# STAC_Test_Board_v1_USB.net
KiCad netlist of a schematic drawn in Altium Designer
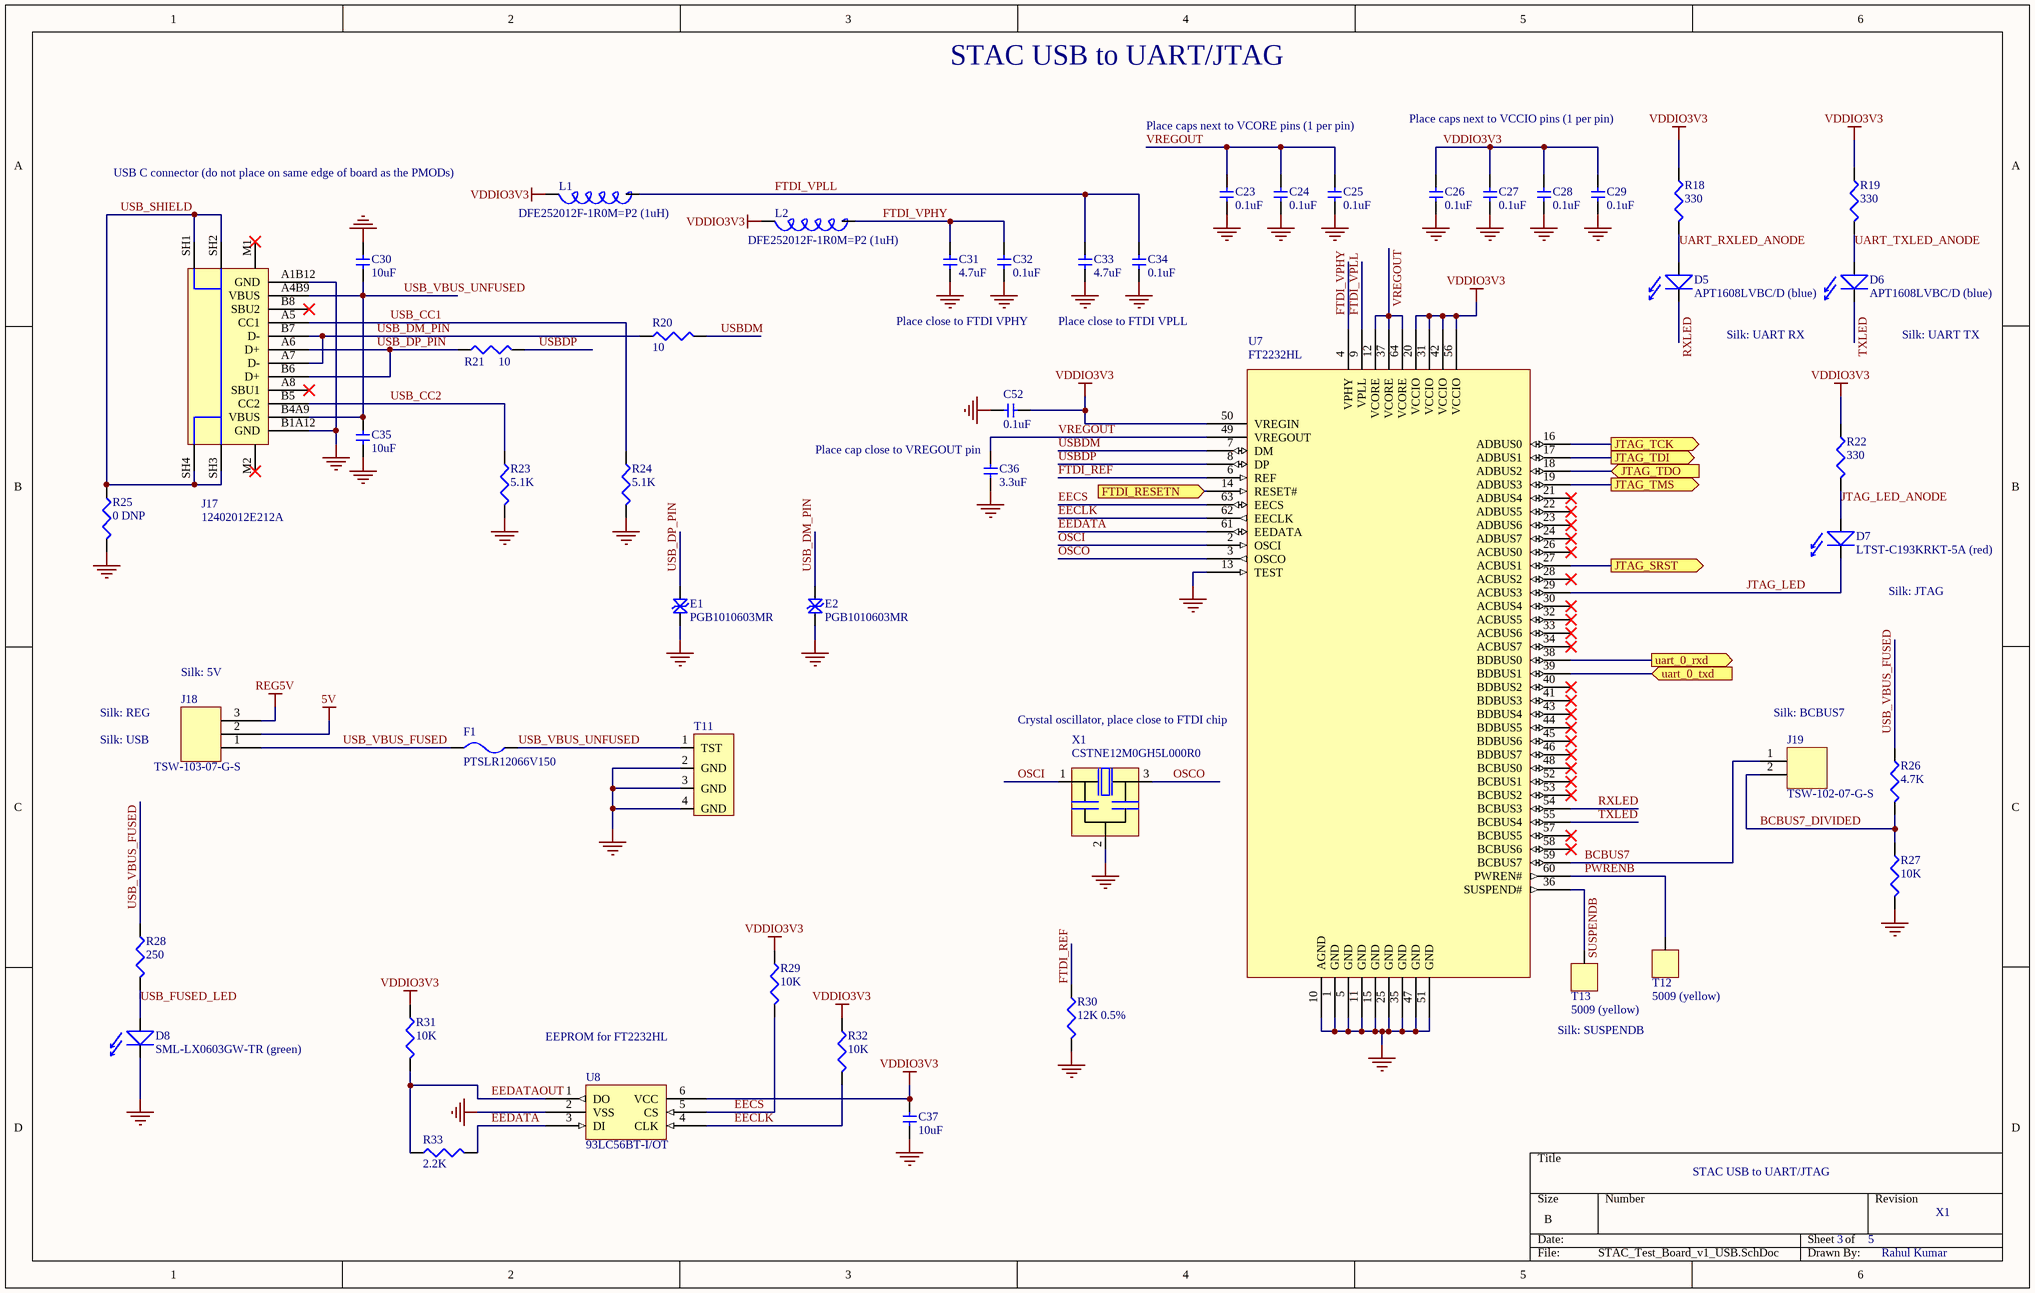
[diagram p0: STAC_Test_Board_v1_USB.SchDoc]

(export (version "E")
  (design (tool "Eeschema 10.0.6"))
  (components
    (comp (ref "C23")
      (value "0.1uF")
      (footprint "0603")
      (description "Capacitor generic")
      (libsource (lib "BWRC") (part "DISCRETE_C"))
    )
    (comp (ref "C24")
      (value "0.1uF")
      (footprint "BWRC:0603")
      (description "Capacitor generic")
      (libsource (lib "BWRC") (part "DISCRETE_C"))
    )
    (comp (ref "C25")
      (value "0.1uF")
      (footprint "BWRC:0603")
      (description "Capacitor generic")
      (libsource (lib "BWRC") (part "DISCRETE_C"))
    )
    (comp (ref "C26")
      (value "0.1uF")
      (footprint "0603")
      (description "Capacitor generic")
      (libsource (lib "BWRC") (part "DISCRETE_C"))
    )
    (comp (ref "C27")
      (value "0.1uF")
      (footprint "0603")
      (description "Capacitor generic")
      (libsource (lib "BWRC") (part "DISCRETE_C"))
    )
    (comp (ref "C28")
      (value "0.1uF")
      (footprint "0603")
      (description "Capacitor generic")
      (libsource (lib "BWRC") (part "DISCRETE_C"))
    )
    (comp (ref "C29")
      (value "0.1uF")
      (footprint "0603")
      (description "Capacitor generic")
      (libsource (lib "BWRC") (part "DISCRETE_C"))
    )
    (comp (ref "C30")
      (value "10uF")
      (footprint "0603")
      (description "Capacitor generic")
      (libsource (lib "BWRC") (part "DISCRETE_C"))
    )
    (comp (ref "C31")
      (value "4.7uF")
      (footprint "BWRC:0603")
      (description "Capacitor generic")
      (libsource (lib "BWRC") (part "DISCRETE_C"))
    )
    (comp (ref "C32")
      (value "0.1uF")
      (footprint "BWRC:0603")
      (description "Capacitor generic")
      (libsource (lib "BWRC") (part "DISCRETE_C"))
    )
    (comp (ref "C33")
      (value "4.7uF")
      (footprint "BWRC:0603")
      (description "Capacitor generic")
      (libsource (lib "BWRC") (part "DISCRETE_C"))
    )
    (comp (ref "C34")
      (value "0.1uF")
      (footprint "BWRC:0603")
      (description "Capacitor generic")
      (libsource (lib "BWRC") (part "DISCRETE_C"))
    )
    (comp (ref "C35")
      (value "10uF")
      (footprint "0603")
      (description "Capacitor generic")
      (libsource (lib "BWRC") (part "DISCRETE_C"))
    )
    (comp (ref "C36")
      (value "3.3uF")
      (footprint "BWRC:0603")
      (description "Capacitor generic")
      (libsource (lib "BWRC") (part "DISCRETE_C"))
    )
    (comp (ref "C37")
      (value "10uF")
      (footprint "BWRC:0603")
      (description "Capacitor generic")
      (libsource (lib "BWRC") (part "DISCRETE_C"))
    )
    (comp (ref "C52")
      (value "0.1uF")
      (footprint "BWRC:0603")
      (description "Capacitor generic")
      (libsource (lib "BWRC") (part "DISCRETE_C"))
    )
    (comp (ref "D5")
      (value "APT1608LVBC/D (blue)")
      (footprint "LED-0603")
      (description "LED generic")
      (libsource (lib "BWRC") (part "DISCRETE_LED"))
    )
    (comp (ref "D6")
      (value "APT1608LVBC/D (blue)")
      (footprint "LED-0603")
      (description "LED generic")
      (libsource (lib "BWRC") (part "DISCRETE_LED"))
    )
    (comp (ref "D7")
      (value "LTST-C193KRKT-5A (red)")
      (footprint "LED-0603")
      (description "LED generic")
      (libsource (lib "BWRC") (part "DISCRETE_LED"))
    )
    (comp (ref "D8")
      (value "SML-LX0603GW-TR (green)")
      (footprint "LED-0603")
      (description "LED generic")
      (libsource (lib "BWRC") (part "DISCRETE_LED"))
    )
    (comp (ref "E1")
      (value "PGB1010603MR")
      (footprint "0603")
      (description "TVS ESD protection clamp generic")
      (libsource (lib "BWRC") (part "DISCRETE_TVS"))
    )
    (comp (ref "E2")
      (value "PGB1010603MR")
      (footprint "0603")
      (description "TVS ESD protection clamp generic")
      (libsource (lib "BWRC") (part "DISCRETE_TVS"))
    )
    (comp (ref "F1")
      (value "PTSLR12066V150")
      (footprint "1206")
      (description "Fuse generic")
      (libsource (lib "BWRC") (part "DISCRETE_F"))
    )
    (comp (ref "J17")
      (value "12402012E212A")
      (footprint "CON-012-0.5-8.90X7.4/USB-C")
      (description "Con 12 pin USB C receptacle + 4 shields, and 2 alignment posts")
      (libsource (lib "BWRC") (part "CON_012pin_USB_C_RECP"))
    )
    (comp (ref "J18")
      (value "TSW-103-07-G-S")
      (footprint "CON-003-100-300X100/1X3-POST")
      (description "Con 3 pins")
      (libsource (lib "BWRC") (part "CON_003pin_1x3"))
    )
    (comp (ref "J19")
      (value "TSW-102-07-G-S")
      (footprint "CON-002-100-200X100/1X2-POST")
      (description "Con 2 pins")
      (libsource (lib "BWRC") (part "CON_002pin_1x2"))
    )
    (comp (ref "L1")
      (value "DFE252012F-1R0M=P2 (1uH)")
      (footprint "1008")
      (description "Inductor generic")
      (libsource (lib "BWRC") (part "DISCRETE_L"))
    )
    (comp (ref "L2")
      (value "DFE252012F-1R0M=P2 (1uH)")
      (footprint "1008")
      (description "Inductor generic")
      (libsource (lib "BWRC") (part "DISCRETE_L"))
    )
    (comp (ref "R18")
      (value "330")
      (footprint "0603")
      (description "Resistor generic")
      (libsource (lib "BWRC") (part "DISCRETE_R"))
    )
    (comp (ref "R19")
      (value "330")
      (footprint "0603")
      (description "Resistor generic")
      (libsource (lib "BWRC") (part "DISCRETE_R"))
    )
    (comp (ref "R20")
      (value "10")
      (footprint "0603")
      (description "Resistor generic")
      (libsource (lib "BWRC") (part "DISCRETE_R"))
    )
    (comp (ref "R21")
      (value "10")
      (footprint "0603")
      (description "Resistor generic")
      (libsource (lib "BWRC") (part "DISCRETE_R"))
    )
    (comp (ref "R22")
      (value "330")
      (footprint "0603")
      (description "Resistor generic")
      (libsource (lib "BWRC") (part "DISCRETE_R"))
    )
    (comp (ref "R23")
      (value "5.1K")
      (footprint "0603")
      (description "5.1kohm resistor")
      (libsource (lib "BWRC") (part "DISCRETE_R"))
    )
    (comp (ref "R24")
      (value "5.1K")
      (footprint "0603")
      (description "5.1kohm resistor")
      (libsource (lib "BWRC") (part "DISCRETE_R"))
    )
    (comp (ref "R25")
      (value "0 DNP")
      (footprint "0603")
      (description "Resistor generic")
      (libsource (lib "BWRC") (part "DISCRETE_R"))
    )
    (comp (ref "R26")
      (value "4.7K")
      (footprint "0603")
      (description "Resistor generic")
      (libsource (lib "BWRC") (part "DISCRETE_R"))
    )
    (comp (ref "R27")
      (value "10K")
      (footprint "0603")
      (description "Resistor generic")
      (libsource (lib "BWRC") (part "DISCRETE_R"))
    )
    (comp (ref "R28")
      (value "250")
      (footprint "0603")
      (description "Resistor generic")
      (libsource (lib "BWRC") (part "DISCRETE_R"))
    )
    (comp (ref "R29")
      (value "10K")
      (footprint "0603")
      (description "Resistor generic")
      (libsource (lib "BWRC") (part "DISCRETE_R"))
    )
    (comp (ref "R30")
      (value "12K 0.5%")
      (footprint "0603")
      (description "Resistor generic")
      (libsource (lib "BWRC") (part "DISCRETE_R"))
    )
    (comp (ref "R31")
      (value "10K")
      (footprint "0603")
      (description "Resistor generic")
      (libsource (lib "BWRC") (part "DISCRETE_R"))
    )
    (comp (ref "R32")
      (value "10K")
      (footprint "0603")
      (description "Resistor generic")
      (libsource (lib "BWRC") (part "DISCRETE_R"))
    )
    (comp (ref "R33")
      (value "2.2K")
      (footprint "0603")
      (description "Resistor generic")
      (libsource (lib "BWRC") (part "DISCRETE_R"))
    )
    (comp (ref "T11")
      (value "TEST_PT_4")
      (footprint "BWRC:TP-04-40/ROUND-THT")
      (description "Test point 4 pads for probing")
      (libsource (lib "BWRC") (part "TEST_PT_4"))
    )
    (comp (ref "T12")
      (value "5009 (yellow)")
      (footprint "TP-63/ROUND-THT")
      (description "Test point 1 pin")
      (libsource (lib "BWRC") (part "TEST_PT"))
    )
    (comp (ref "T13")
      (value "5009 (yellow)")
      (footprint "TP-63/ROUND-THT")
      (description "Test point 1 pin")
      (libsource (lib "BWRC") (part "TEST_PT"))
    )
    (comp (ref "U7")
      (value "FT2232HL")
      (footprint "QFP-64-.5-12.0X12.0")
      (description "USB Hi-Speed to Dual Channel Serial UART/FIFO/JTAG/SPI/I2C IC 64-pin LQFP package")
      (libsource (lib "BWRC") (part "IC_FT2232HL"))
    )
    (comp (ref "U8")
      (value "93LC56BT-I/OT")
      (footprint "SOT-23-6")
      (description "EEPROM Non-Volatile Memory 2kbit 128x16 2MHz 2.5V-5.5V SOT-23-6")
      (libsource (lib "BWRC") (part "IC_93LC56BT-I/OT"))
    )
    (comp (ref "X1")
      (value "CSTNE12M0GH5L000R0")
      (footprint "XTAL-03-1.2-3.2X1.3/MURATA")
      (description "crystal oscillator with internal loading capacitors, 3 pins (input, GND, output)")
      (libsource (lib "BWRC") (part "XTALOSC_CAP"))
    )
  )
  (nets
    (net (code "1") (name "/BCBUS7") (class "Default")
      (node (ref "J19") (pin "1") (pinfunction "1_1") (pintype "passive"))
      (node (ref "U7") (pin "59") (pinfunction "BCBUS7_59") (pintype "bidirectional"))
    )
    (net (code "2") (name "/BCBUS7_DIVIDED") (class "Default")
      (node (ref "J19") (pin "2") (pinfunction "2_2") (pintype "passive"))
      (node (ref "R26") (pin "2") (pinfunction "2_2") (pintype "passive"))
      (node (ref "R27") (pin "1") (pinfunction "1_1") (pintype "passive"))
    )
    (net (code "3") (name "/EECLK") (class "Default")
      (node (ref "R32") (pin "2") (pinfunction "2_2") (pintype "passive"))
      (node (ref "U7") (pin "62") (pinfunction "EECLK_62") (pintype "output"))
      (node (ref "U8") (pin "4") (pinfunction "CLK_4") (pintype "input"))
    )
    (net (code "4") (name "/EECS") (class "Default")
      (node (ref "R29") (pin "2") (pinfunction "2_2") (pintype "passive"))
      (node (ref "U7") (pin "63") (pinfunction "EECS_63") (pintype "bidirectional"))
      (node (ref "U8") (pin "5") (pinfunction "CS_5") (pintype "input"))
    )
    (net (code "5") (name "/EEDATA") (class "Default")
      (node (ref "R33") (pin "2") (pinfunction "2_2") (pintype "passive"))
      (node (ref "U7") (pin "61") (pinfunction "EEDATA_61") (pintype "bidirectional"))
      (node (ref "U8") (pin "3") (pinfunction "DI_3") (pintype "input"))
    )
    (net (code "6") (name "/EEDATAOUT") (class "Default")
      (node (ref "R31") (pin "2") (pinfunction "2_2") (pintype "passive"))
      (node (ref "R33") (pin "1") (pinfunction "1_1") (pintype "passive"))
      (node (ref "U8") (pin "1") (pinfunction "DO_1") (pintype "output"))
    )
    (net (code "7") (name "/FTDI_REF") (class "Default")
      (node (ref "R30") (pin "1") (pinfunction "1_1") (pintype "passive"))
      (node (ref "U7") (pin "6") (pinfunction "REF_6") (pintype "input"))
    )
    (net (code "8") (name "/FTDI_RESETN") (class "Default")
      (node (ref "U7") (pin "14") (pinfunction "RESET#_14") (pintype "input"))
    )
    (net (code "9") (name "/FTDI_VPHY") (class "Default")
      (node (ref "C31") (pin "1") (pinfunction "1_1") (pintype "passive"))
      (node (ref "C32") (pin "1") (pinfunction "1_1") (pintype "passive"))
      (node (ref "L2") (pin "1") (pinfunction "1_1") (pintype "passive"))
      (node (ref "U7") (pin "4") (pinfunction "VPHY_4") (pintype "power_in"))
    )
    (net (code "10") (name "/FTDI_VPLL") (class "Default")
      (node (ref "C33") (pin "1") (pinfunction "1_1") (pintype "passive"))
      (node (ref "C34") (pin "1") (pinfunction "1_1") (pintype "passive"))
      (node (ref "L1") (pin "1") (pinfunction "1_1") (pintype "passive"))
      (node (ref "U7") (pin "9") (pinfunction "VPLL_9") (pintype "power_in"))
    )
    (net (code "11") (name "/JTAG_LED") (class "Default")
      (node (ref "D7") (pin "1") (pinfunction "1_1") (pintype "passive"))
      (node (ref "U7") (pin "29") (pinfunction "ACBUS3_29") (pintype "bidirectional"))
    )
    (net (code "12") (name "/JTAG_LED_ANODE") (class "Default")
      (node (ref "D7") (pin "2") (pinfunction "2_2") (pintype "passive"))
      (node (ref "R22") (pin "2") (pinfunction "2_2") (pintype "passive"))
    )
    (net (code "13") (name "/JTAG_SRST") (class "Default")
      (node (ref "U7") (pin "27") (pinfunction "ACBUS1_27") (pintype "bidirectional"))
    )
    (net (code "14") (name "/JTAG_TCK") (class "Default")
      (node (ref "U7") (pin "16") (pinfunction "ADBUS0_16") (pintype "bidirectional"))
    )
    (net (code "15") (name "/JTAG_TDI") (class "Default")
      (node (ref "U7") (pin "17") (pinfunction "ADBUS1_17") (pintype "bidirectional"))
    )
    (net (code "16") (name "/JTAG_TDO") (class "Default")
      (node (ref "U7") (pin "18") (pinfunction "ADBUS2_18") (pintype "bidirectional"))
    )
    (net (code "17") (name "/JTAG_TMS") (class "Default")
      (node (ref "U7") (pin "19") (pinfunction "ADBUS3_19") (pintype "bidirectional"))
    )
    (net (code "18") (name "/OSCI") (class "Default")
      (node (ref "U7") (pin "2") (pinfunction "OSCI_2") (pintype "input"))
      (node (ref "X1") (pin "1") (pinfunction "INPUT_1") (pintype "passive"))
    )
    (net (code "19") (name "/OSCO") (class "Default")
      (node (ref "U7") (pin "3") (pinfunction "OSCO_3") (pintype "output"))
      (node (ref "X1") (pin "3") (pinfunction "OUTPUT_3") (pintype "passive"))
    )
    (net (code "20") (name "/PWRENB") (class "Default")
      (node (ref "T12") (pin "1") (pinfunction "1_1") (pintype "passive"))
      (node (ref "U7") (pin "60") (pinfunction "PWREN#_60") (pintype "output"))
    )
    (net (code "21") (name "/RXLED") (class "Default")
      (node (ref "D5") (pin "1") (pinfunction "1_1") (pintype "passive"))
      (node (ref "U7") (pin "54") (pinfunction "BCBUS3_54") (pintype "bidirectional"))
    )
    (net (code "22") (name "/SUSPENDB") (class "Default")
      (node (ref "T13") (pin "1") (pinfunction "1_1") (pintype "passive"))
      (node (ref "U7") (pin "36") (pinfunction "SUSPEND#_36") (pintype "output"))
    )
    (net (code "23") (name "/TXLED") (class "Default")
      (node (ref "D6") (pin "1") (pinfunction "1_1") (pintype "passive"))
      (node (ref "U7") (pin "55") (pinfunction "BCBUS4_55") (pintype "bidirectional"))
    )
    (net (code "24") (name "/UART_RXLED_ANODE") (class "Default")
      (node (ref "D5") (pin "2") (pinfunction "2_2") (pintype "passive"))
      (node (ref "R18") (pin "2") (pinfunction "2_2") (pintype "passive"))
    )
    (net (code "25") (name "/UART_TXLED_ANODE") (class "Default")
      (node (ref "D6") (pin "2") (pinfunction "2_2") (pintype "passive"))
      (node (ref "R19") (pin "2") (pinfunction "2_2") (pintype "passive"))
    )
    (net (code "26") (name "/USBDM") (class "Default")
      (node (ref "R20") (pin "2") (pinfunction "2_2") (pintype "passive"))
      (node (ref "U7") (pin "7") (pinfunction "DM_7") (pintype "bidirectional"))
    )
    (net (code "27") (name "/USBDP") (class "Default")
      (node (ref "R21") (pin "2") (pinfunction "2_2") (pintype "passive"))
      (node (ref "U7") (pin "8") (pinfunction "DP_8") (pintype "bidirectional"))
    )
    (net (code "28") (name "/USB_CC1") (class "Default")
      (node (ref "J17") (pin "A5") (pinfunction "CC1_A5") (pintype "passive"))
      (node (ref "R24") (pin "1") (pinfunction "1_1") (pintype "passive"))
    )
    (net (code "29") (name "/USB_CC2") (class "Default")
      (node (ref "J17") (pin "B5") (pinfunction "CC2_B5") (pintype "power_in"))
      (node (ref "R23") (pin "1") (pinfunction "1_1") (pintype "passive"))
    )
    (net (code "30") (name "/USB_DM_PIN") (class "Default")
      (node (ref "E2") (pin "1") (pinfunction "1_1") (pintype "passive"))
      (node (ref "J17") (pin "A7") (pinfunction "D-_A7") (pintype "passive"))
      (node (ref "J17") (pin "B7") (pinfunction "D-_B7") (pintype "passive"))
      (node (ref "R20") (pin "1") (pinfunction "1_1") (pintype "passive"))
    )
    (net (code "31") (name "/USB_DP_PIN") (class "Default")
      (node (ref "E1") (pin "1") (pinfunction "1_1") (pintype "passive"))
      (node (ref "J17") (pin "A6") (pinfunction "D+_A6") (pintype "passive"))
      (node (ref "J17") (pin "B6") (pinfunction "D+_B6") (pintype "passive"))
      (node (ref "R21") (pin "1") (pinfunction "1_1") (pintype "passive"))
    )
    (net (code "32") (name "/USB_FUSED_LED") (class "Default")
      (node (ref "D8") (pin "2") (pinfunction "2_2") (pintype "passive"))
      (node (ref "R28") (pin "2") (pinfunction "2_2") (pintype "passive"))
    )
    (net (code "33") (name "/USB_SHIELD") (class "Default")
      (node (ref "J17") (pin "SH1") (pintype "passive"))
      (node (ref "J17") (pin "SH2") (pintype "passive"))
      (node (ref "J17") (pin "SH3") (pintype "passive"))
      (node (ref "J17") (pin "SH4") (pintype "passive"))
      (node (ref "R25") (pin "1") (pinfunction "1_1") (pintype "passive"))
    )
    (net (code "34") (name "/USB_VBUS_FUSED") (class "Default")
      (node (ref "F1") (pin "2") (pinfunction "2_2") (pintype "passive"))
      (node (ref "J18") (pin "1") (pinfunction "1_1") (pintype "passive"))
      (node (ref "R26") (pin "1") (pinfunction "1_1") (pintype "passive"))
      (node (ref "R28") (pin "1") (pinfunction "1_1") (pintype "passive"))
    )
    (net (code "35") (name "/USB_VBUS_UNFUSED") (class "Default")
      (node (ref "C30") (pin "2") (pinfunction "2_2") (pintype "passive"))
      (node (ref "C35") (pin "1") (pinfunction "1_1") (pintype "passive"))
      (node (ref "F1") (pin "1") (pinfunction "1_1") (pintype "passive"))
      (node (ref "J17") (pin "A4B9") (pinfunction "VBUS_A4B9") (pintype "passive"))
      (node (ref "J17") (pin "B4A9") (pinfunction "VBUS_B4A9") (pintype "passive"))
      (node (ref "T11") (pin "1") (pinfunction "TST_1") (pintype "passive"))
    )
    (net (code "36") (name "/VREGOUT") (class "Default")
      (node (ref "C23") (pin "1") (pinfunction "1_1") (pintype "passive"))
      (node (ref "C24") (pin "1") (pinfunction "1_1") (pintype "passive"))
      (node (ref "C25") (pin "1") (pinfunction "1_1") (pintype "passive"))
      (node (ref "C36") (pin "1") (pinfunction "1_1") (pintype "passive"))
      (node (ref "U7") (pin "12") (pinfunction "VCORE_12") (pintype "power_in"))
      (node (ref "U7") (pin "37") (pinfunction "VCORE_37") (pintype "power_in"))
      (node (ref "U7") (pin "49") (pinfunction "VREGOUT_49") (pintype "power_in"))
      (node (ref "U7") (pin "64") (pinfunction "VCORE_64") (pintype "power_in"))
    )
    (net (code "37") (name "/uart_0_rxd") (class "Default")
      (node (ref "U7") (pin "38") (pinfunction "BDBUS0_38") (pintype "bidirectional"))
    )
    (net (code "38") (name "/uart_0_txd") (class "Default")
      (node (ref "U7") (pin "39") (pinfunction "BDBUS1_39") (pintype "bidirectional"))
    )
    (net (code "39") (name "5V") (class "Default")
      (node (ref "J18") (pin "2") (pinfunction "2_2") (pintype "passive"))
    )
    (net (code "40") (name "GND") (class "Default")
      (node (ref "C23") (pin "2") (pinfunction "2_2") (pintype "passive"))
      (node (ref "C24") (pin "2") (pinfunction "2_2") (pintype "passive"))
      (node (ref "C25") (pin "2") (pinfunction "2_2") (pintype "passive"))
      (node (ref "C26") (pin "2") (pinfunction "2_2") (pintype "passive"))
      (node (ref "C27") (pin "2") (pinfunction "2_2") (pintype "passive"))
      (node (ref "C28") (pin "2") (pinfunction "2_2") (pintype "passive"))
      (node (ref "C29") (pin "2") (pinfunction "2_2") (pintype "passive"))
      (node (ref "C30") (pin "1") (pinfunction "1_1") (pintype "passive"))
      (node (ref "C31") (pin "2") (pinfunction "2_2") (pintype "passive"))
      (node (ref "C32") (pin "2") (pinfunction "2_2") (pintype "passive"))
      (node (ref "C33") (pin "2") (pinfunction "2_2") (pintype "passive"))
      (node (ref "C34") (pin "2") (pinfunction "2_2") (pintype "passive"))
      (node (ref "C35") (pin "2") (pinfunction "2_2") (pintype "passive"))
      (node (ref "C36") (pin "2") (pinfunction "2_2") (pintype "passive"))
      (node (ref "C37") (pin "2") (pinfunction "2_2") (pintype "passive"))
      (node (ref "C52") (pin "1") (pinfunction "1_1") (pintype "passive"))
      (node (ref "D8") (pin "1") (pinfunction "1_1") (pintype "passive"))
      (node (ref "E1") (pin "2") (pinfunction "2_2") (pintype "passive"))
      (node (ref "E2") (pin "2") (pinfunction "2_2") (pintype "passive"))
      (node (ref "J17") (pin "A1B12") (pinfunction "GND_A1B12") (pintype "passive"))
      (node (ref "J17") (pin "B1A12") (pinfunction "GND_B1A12") (pintype "passive"))
      (node (ref "R23") (pin "2") (pinfunction "2_2") (pintype "passive"))
      (node (ref "R24") (pin "2") (pinfunction "2_2") (pintype "passive"))
      (node (ref "R25") (pin "2") (pinfunction "2_2") (pintype "passive"))
      (node (ref "R27") (pin "2") (pinfunction "2_2") (pintype "passive"))
      (node (ref "R30") (pin "2") (pinfunction "2_2") (pintype "passive"))
      (node (ref "T11") (pin "2") (pinfunction "GND_2") (pintype "passive"))
      (node (ref "T11") (pin "3") (pinfunction "GND_3") (pintype "passive"))
      (node (ref "T11") (pin "4") (pinfunction "GND_4") (pintype "passive"))
      (node (ref "U7") (pin "1") (pinfunction "GND_1") (pintype "power_in"))
      (node (ref "U7") (pin "10") (pinfunction "AGND_10") (pintype "power_in"))
      (node (ref "U7") (pin "11") (pinfunction "GND_11") (pintype "power_in"))
      (node (ref "U7") (pin "13") (pinfunction "TEST_13") (pintype "input"))
      (node (ref "U7") (pin "15") (pinfunction "GND_15") (pintype "power_in"))
      (node (ref "U7") (pin "25") (pinfunction "GND_25") (pintype "power_in"))
      (node (ref "U7") (pin "35") (pinfunction "GND_35") (pintype "power_in"))
      (node (ref "U7") (pin "47") (pinfunction "GND_47") (pintype "power_in"))
      (node (ref "U7") (pin "5") (pinfunction "GND_5") (pintype "power_in"))
      (node (ref "U7") (pin "51") (pinfunction "GND_51") (pintype "power_in"))
      (node (ref "U8") (pin "2") (pinfunction "VSS_2") (pintype "power_in"))
      (node (ref "X1") (pin "2") (pinfunction "GND_2") (pintype "passive"))
    )
    (net (code "41") (name "REG5V") (class "Default")
      (node (ref "J18") (pin "3") (pinfunction "3_3") (pintype "passive"))
    )
    (net (code "42") (name "VDDIO3V3") (class "Default")
      (node (ref "C26") (pin "1") (pinfunction "1_1") (pintype "passive"))
      (node (ref "C27") (pin "1") (pinfunction "1_1") (pintype "passive"))
      (node (ref "C28") (pin "1") (pinfunction "1_1") (pintype "passive"))
      (node (ref "C29") (pin "1") (pinfunction "1_1") (pintype "passive"))
      (node (ref "C37") (pin "1") (pinfunction "1_1") (pintype "passive"))
      (node (ref "C52") (pin "2") (pinfunction "2_2") (pintype "passive"))
      (node (ref "L1") (pin "2") (pinfunction "2_2") (pintype "passive"))
      (node (ref "L2") (pin "2") (pinfunction "2_2") (pintype "passive"))
      (node (ref "R18") (pin "1") (pinfunction "1_1") (pintype "passive"))
      (node (ref "R19") (pin "1") (pinfunction "1_1") (pintype "passive"))
      (node (ref "R22") (pin "1") (pinfunction "1_1") (pintype "passive"))
      (node (ref "R29") (pin "1") (pinfunction "1_1") (pintype "passive"))
      (node (ref "R31") (pin "1") (pinfunction "1_1") (pintype "passive"))
      (node (ref "R32") (pin "1") (pinfunction "1_1") (pintype "passive"))
      (node (ref "U7") (pin "20") (pinfunction "VCCIO_20") (pintype "power_in"))
      (node (ref "U7") (pin "31") (pinfunction "VCCIO_31") (pintype "power_in"))
      (node (ref "U7") (pin "42") (pinfunction "VCCIO_42") (pintype "power_in"))
      (node (ref "U7") (pin "50") (pinfunction "VREGIN_50") (pintype "power_in"))
      (node (ref "U7") (pin "56") (pinfunction "VCCIO_56") (pintype "power_in"))
      (node (ref "U8") (pin "6") (pinfunction "VCC_6") (pintype "power_in"))
    )
    (net (code "43") (name "unconnected-(J17-PadM1)") (class "Default")
      (node (ref "J17") (pin "M1") (pintype "passive+no_connect"))
    )
    (net (code "44") (name "unconnected-(J17-PadM2)") (class "Default")
      (node (ref "J17") (pin "M2") (pintype "passive+no_connect"))
    )
    (net (code "45") (name "unconnected-(J17-SBU1-PadA8)") (class "Default")
      (node (ref "J17") (pin "A8") (pinfunction "SBU1_A8") (pintype "passive+no_connect"))
    )
    (net (code "46") (name "unconnected-(J17-SBU2-PadB8)") (class "Default")
      (node (ref "J17") (pin "B8") (pinfunction "SBU2_B8") (pintype "passive+no_connect"))
    )
    (net (code "47") (name "unconnected-(U7-ACBUS0-Pad26)") (class "Default")
      (node (ref "U7") (pin "26") (pinfunction "ACBUS0_26") (pintype "bidirectional+no_connect"))
    )
    (net (code "48") (name "unconnected-(U7-ACBUS2-Pad28)") (class "Default")
      (node (ref "U7") (pin "28") (pinfunction "ACBUS2_28") (pintype "bidirectional+no_connect"))
    )
    (net (code "49") (name "unconnected-(U7-ACBUS4-Pad30)") (class "Default")
      (node (ref "U7") (pin "30") (pinfunction "ACBUS4_30") (pintype "bidirectional+no_connect"))
    )
    (net (code "50") (name "unconnected-(U7-ACBUS5-Pad32)") (class "Default")
      (node (ref "U7") (pin "32") (pinfunction "ACBUS5_32") (pintype "bidirectional+no_connect"))
    )
    (net (code "51") (name "unconnected-(U7-ACBUS6-Pad33)") (class "Default")
      (node (ref "U7") (pin "33") (pinfunction "ACBUS6_33") (pintype "bidirectional+no_connect"))
    )
    (net (code "52") (name "unconnected-(U7-ACBUS7-Pad34)") (class "Default")
      (node (ref "U7") (pin "34") (pinfunction "ACBUS7_34") (pintype "bidirectional+no_connect"))
    )
    (net (code "53") (name "unconnected-(U7-ADBUS4-Pad21)") (class "Default")
      (node (ref "U7") (pin "21") (pinfunction "ADBUS4_21") (pintype "bidirectional+no_connect"))
    )
    (net (code "54") (name "unconnected-(U7-ADBUS5-Pad22)") (class "Default")
      (node (ref "U7") (pin "22") (pinfunction "ADBUS5_22") (pintype "bidirectional+no_connect"))
    )
    (net (code "55") (name "unconnected-(U7-ADBUS6-Pad23)") (class "Default")
      (node (ref "U7") (pin "23") (pinfunction "ADBUS6_23") (pintype "bidirectional+no_connect"))
    )
    (net (code "56") (name "unconnected-(U7-ADBUS7-Pad24)") (class "Default")
      (node (ref "U7") (pin "24") (pinfunction "ADBUS7_24") (pintype "bidirectional+no_connect"))
    )
    (net (code "57") (name "unconnected-(U7-BCBUS0-Pad48)") (class "Default")
      (node (ref "U7") (pin "48") (pinfunction "BCBUS0_48") (pintype "bidirectional+no_connect"))
    )
    (net (code "58") (name "unconnected-(U7-BCBUS1-Pad52)") (class "Default")
      (node (ref "U7") (pin "52") (pinfunction "BCBUS1_52") (pintype "bidirectional+no_connect"))
    )
    (net (code "59") (name "unconnected-(U7-BCBUS2-Pad53)") (class "Default")
      (node (ref "U7") (pin "53") (pinfunction "BCBUS2_53") (pintype "bidirectional+no_connect"))
    )
    (net (code "60") (name "unconnected-(U7-BCBUS5-Pad57)") (class "Default")
      (node (ref "U7") (pin "57") (pinfunction "BCBUS5_57") (pintype "bidirectional+no_connect"))
    )
    (net (code "61") (name "unconnected-(U7-BCBUS6-Pad58)") (class "Default")
      (node (ref "U7") (pin "58") (pinfunction "BCBUS6_58") (pintype "bidirectional+no_connect"))
    )
    (net (code "62") (name "unconnected-(U7-BDBUS2-Pad40)") (class "Default")
      (node (ref "U7") (pin "40") (pinfunction "BDBUS2_40") (pintype "bidirectional+no_connect"))
    )
    (net (code "63") (name "unconnected-(U7-BDBUS3-Pad41)") (class "Default")
      (node (ref "U7") (pin "41") (pinfunction "BDBUS3_41") (pintype "bidirectional+no_connect"))
    )
    (net (code "64") (name "unconnected-(U7-BDBUS4-Pad43)") (class "Default")
      (node (ref "U7") (pin "43") (pinfunction "BDBUS4_43") (pintype "bidirectional+no_connect"))
    )
    (net (code "65") (name "unconnected-(U7-BDBUS5-Pad44)") (class "Default")
      (node (ref "U7") (pin "44") (pinfunction "BDBUS5_44") (pintype "bidirectional+no_connect"))
    )
    (net (code "66") (name "unconnected-(U7-BDBUS6-Pad45)") (class "Default")
      (node (ref "U7") (pin "45") (pinfunction "BDBUS6_45") (pintype "bidirectional+no_connect"))
    )
    (net (code "67") (name "unconnected-(U7-BDBUS7-Pad46)") (class "Default")
      (node (ref "U7") (pin "46") (pinfunction "BDBUS7_46") (pintype "bidirectional+no_connect"))
    )
  )
)
